# piezo-preamp-tickler_V2-RevX.net
KiCad netlist of a schematic drawn in EAGLE
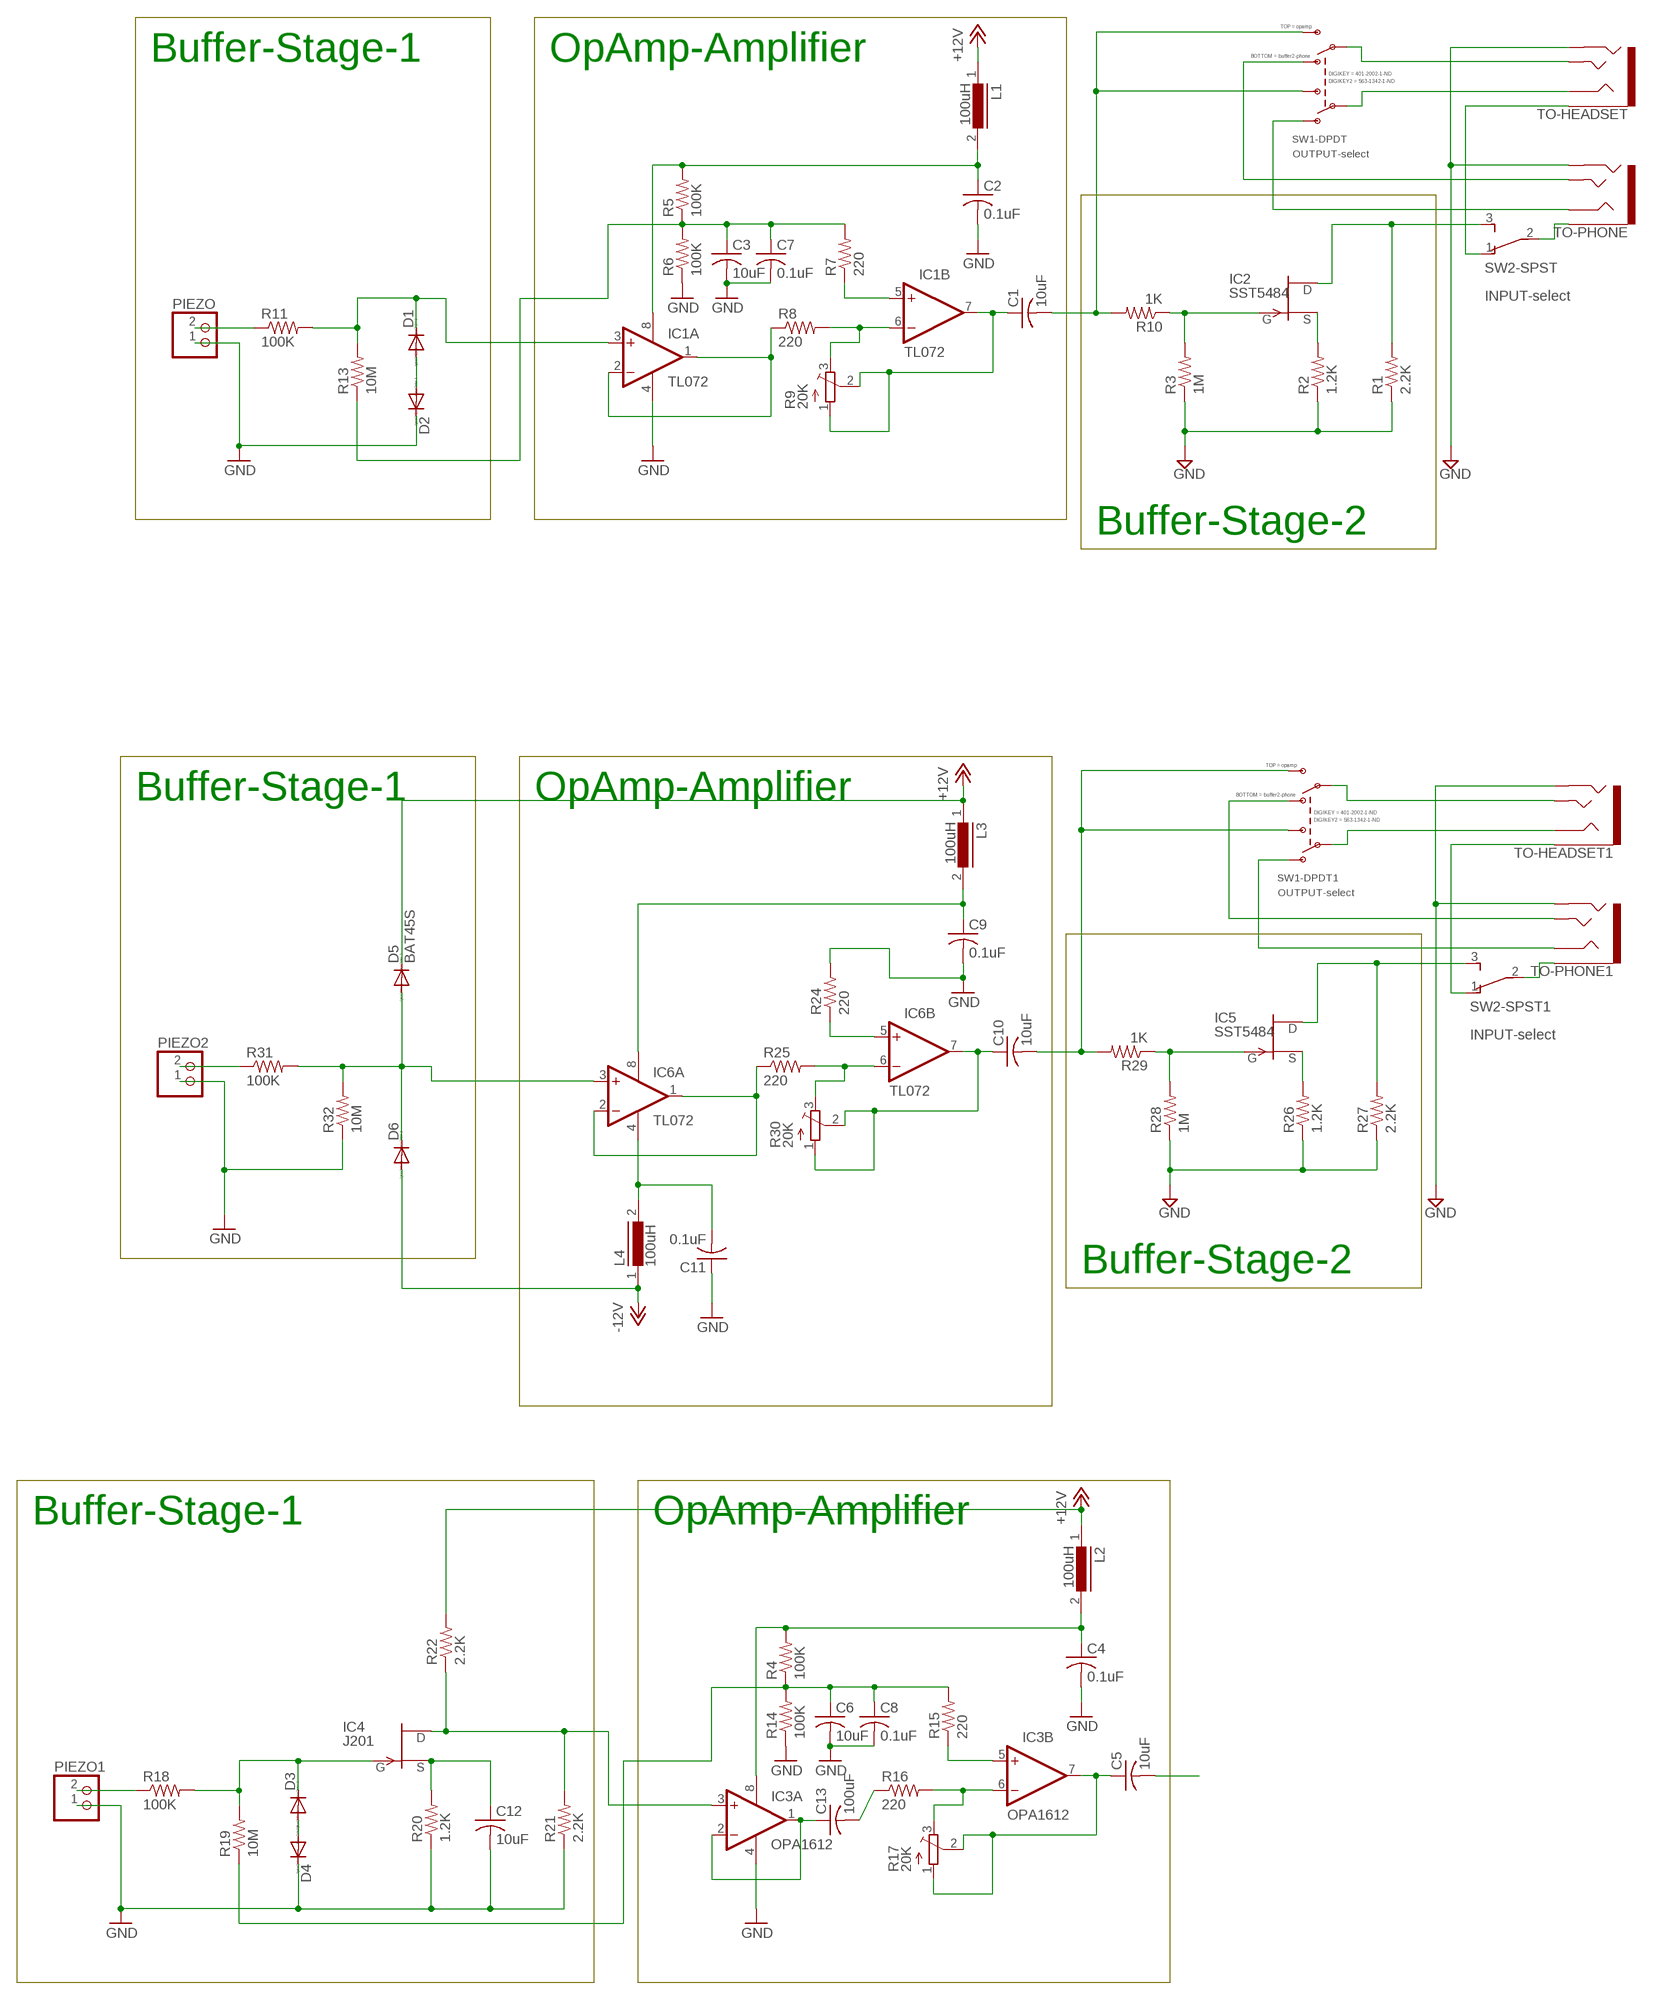
[diagram p0: schematic, sheet 1]
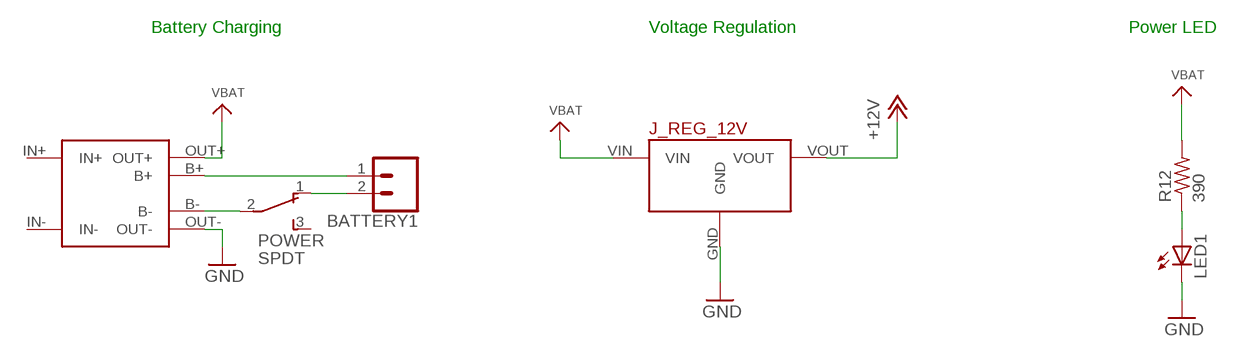
[diagram p1: schematic, sheet 2]

(export (version "E")
  (design (tool "Eeschema 10.0.6"))
  (components
    (comp (ref "C1")
      (value "10uF")
      (footprint "eagle-import:C0805K")
      (libsource (lib "eagle-import") (part "C-USC0805K"))
    )
    (comp (ref "C2")
      (value "0.1uF")
      (footprint "eagle-import:C0805K")
      (libsource (lib "eagle-import") (part "C-USC0805K"))
    )
    (comp (ref "C3")
      (value "10uF")
      (footprint "eagle-import:C0805K")
      (libsource (lib "eagle-import") (part "C-USC0805K"))
    )
    (comp (ref "C4")
      (value "0.1uF")
      (footprint "eagle-import:C0805K")
      (libsource (lib "eagle-import") (part "C-USC0805K"))
    )
    (comp (ref "C5")
      (value "10uF")
      (footprint "eagle-import:C0805K")
      (libsource (lib "eagle-import") (part "C-USC0805K"))
    )
    (comp (ref "C6")
      (value "10uF")
      (footprint "eagle-import:C0805K")
      (libsource (lib "eagle-import") (part "C-USC0805K"))
    )
    (comp (ref "C7")
      (value "0.1uF")
      (footprint "eagle-import:C0805K")
      (libsource (lib "eagle-import") (part "C-USC0805K"))
    )
    (comp (ref "C8")
      (value "0.1uF")
      (footprint "eagle-import:C0805K")
      (libsource (lib "eagle-import") (part "C-USC0805K"))
    )
    (comp (ref "C9")
      (value "0.1uF")
      (footprint "eagle-import:C0805K")
      (libsource (lib "eagle-import") (part "C-USC0805K"))
    )
    (comp (ref "C10")
      (value "10uF")
      (footprint "eagle-import:C0805K")
      (libsource (lib "eagle-import") (part "C-USC0805K"))
    )
    (comp (ref "C11")
      (value "0.1uF")
      (footprint "eagle-import:C0805K")
      (libsource (lib "eagle-import") (part "C-USC0805K"))
    )
    (comp (ref "C12")
      (value "10uF")
      (footprint "eagle-import:C0805K")
      (libsource (lib "eagle-import") (part "C-USC0805K"))
    )
    (comp (ref "C13")
      (value "100uF")
      (footprint "eagle-import:C0805K")
      (libsource (lib "eagle-import") (part "C-USC0805K"))
    )
    (comp (ref "D1")
      (value "DIODE-SOD123")
      (footprint "eagle-import:SOD123")
      (libsource (lib "eagle-import") (part "DIODE-SOD123"))
    )
    (comp (ref "D2")
      (value "DIODE-SOD123")
      (footprint "eagle-import:SOD123")
      (libsource (lib "eagle-import") (part "DIODE-SOD123"))
    )
    (comp (ref "D3")
      (value "DIODE-SOD123")
      (footprint "eagle-import:SOD123")
      (libsource (lib "eagle-import") (part "DIODE-SOD123"))
    )
    (comp (ref "D4")
      (value "DIODE-SOD123")
      (footprint "eagle-import:SOD123")
      (libsource (lib "eagle-import") (part "DIODE-SOD123"))
    )
    (comp (ref "D5")
      (value "BAT45S")
      (footprint "eagle-import:SOD123")
      (libsource (lib "eagle-import") (part "DIODE-SOD123"))
    )
    (comp (ref "D6")
      (value "DIODE-SOD123")
      (footprint "eagle-import:SOD123")
      (libsource (lib "eagle-import") (part "DIODE-SOD123"))
    )
    (comp (ref "IC1")
      (value "TL072")
      (footprint "eagle-import:SO08")
      (libsource (lib "eagle-import") (part "OPA2UA134"))
    )
    (comp (ref "IC2")
      (value "SST5484")
      (footprint "eagle-import:SOT23")
      (libsource (lib "eagle-import") (part "?548SST4"))
    )
    (comp (ref "IC3")
      (value "OPA1612")
      (footprint "eagle-import:SO08")
      (libsource (lib "eagle-import") (part "OPA2UA134"))
    )
    (comp (ref "IC4")
      (value "J201")
      (footprint "eagle-import:SOT23")
      (libsource (lib "eagle-import") (part "?548SST4"))
    )
    (comp (ref "IC5")
      (value "SST5484")
      (footprint "eagle-import:SOT23")
      (libsource (lib "eagle-import") (part "?548SST4"))
    )
    (comp (ref "IC6")
      (value "TL072")
      (footprint "eagle-import:SO08")
      (libsource (lib "eagle-import") (part "OPA2UA134"))
    )
    (comp (ref "L1")
      (value "100uH")
      (footprint "eagle-import:LBC-SE")
      (libsource (lib "eagle-import") (part "LBC-SE"))
    )
    (comp (ref "L2")
      (value "100uH")
      (footprint "eagle-import:LBC-SE")
      (libsource (lib "eagle-import") (part "LBC-SE"))
    )
    (comp (ref "L3")
      (value "100uH")
      (footprint "eagle-import:LBC-SE")
      (libsource (lib "eagle-import") (part "LBC-SE"))
    )
    (comp (ref "L4")
      (value "100uH")
      (footprint "eagle-import:LBC-SE")
      (libsource (lib "eagle-import") (part "LBC-SE"))
    )
    (comp (ref "PIEZO")
      (value "JST_2PIN-THM")
      (footprint "eagle-import:JST-PH-2-THM")
      (libsource (lib "eagle-import") (part "JST_2PIN-THM"))
    )
    (comp (ref "PIEZO1")
      (value "JST_2PIN-THM")
      (footprint "eagle-import:JST-PH-2-THM")
      (libsource (lib "eagle-import") (part "JST_2PIN-THM"))
    )
    (comp (ref "PIEZO2")
      (value "JST_2PIN-THM")
      (footprint "eagle-import:JST-PH-2-THM")
      (libsource (lib "eagle-import") (part "JST_2PIN-THM"))
    )
    (comp (ref "R1")
      (value "2.2K")
      (footprint "eagle-import:R0603")
      (libsource (lib "eagle-import") (part "R-US_R0603"))
    )
    (comp (ref "R2")
      (value "1.2K")
      (footprint "eagle-import:R0603")
      (libsource (lib "eagle-import") (part "R-US_R0603"))
    )
    (comp (ref "R3")
      (value "1M")
      (footprint "eagle-import:R0603")
      (libsource (lib "eagle-import") (part "R-US_R0603"))
    )
    (comp (ref "R4")
      (value "100K")
      (footprint "eagle-import:R0603")
      (libsource (lib "eagle-import") (part "R-US_R0603"))
    )
    (comp (ref "R5")
      (value "100K")
      (footprint "eagle-import:R0603")
      (libsource (lib "eagle-import") (part "R-US_R0603"))
    )
    (comp (ref "R6")
      (value "100K")
      (footprint "eagle-import:R0603")
      (libsource (lib "eagle-import") (part "R-US_R0603"))
    )
    (comp (ref "R7")
      (value "220")
      (footprint "eagle-import:R0603")
      (libsource (lib "eagle-import") (part "R-US_R0603"))
    )
    (comp (ref "R8")
      (value "220")
      (footprint "eagle-import:R0603")
      (libsource (lib "eagle-import") (part "R-US_R0603"))
    )
    (comp (ref "R9")
      (value "20K")
      (footprint "eagle-import:TC33X")
      (libsource (lib "eagle-import") (part "TRIMPOTTC33X"))
    )
    (comp (ref "R10")
      (value "1K")
      (footprint "eagle-import:R0603")
      (libsource (lib "eagle-import") (part "R-US_R0603"))
    )
    (comp (ref "R11")
      (value "100K")
      (footprint "eagle-import:R0603")
      (libsource (lib "eagle-import") (part "R-US_R0603"))
    )
    (comp (ref "R13")
      (value "10M")
      (footprint "eagle-import:R0603")
      (libsource (lib "eagle-import") (part "R-US_R0603"))
    )
    (comp (ref "R14")
      (value "100K")
      (footprint "eagle-import:R0603")
      (libsource (lib "eagle-import") (part "R-US_R0603"))
    )
    (comp (ref "R15")
      (value "220")
      (footprint "eagle-import:R0603")
      (libsource (lib "eagle-import") (part "R-US_R0603"))
    )
    (comp (ref "R16")
      (value "220")
      (footprint "eagle-import:R0603")
      (libsource (lib "eagle-import") (part "R-US_R0603"))
    )
    (comp (ref "R17")
      (value "20K")
      (footprint "eagle-import:TC33X")
      (libsource (lib "eagle-import") (part "TRIMPOTTC33X"))
    )
    (comp (ref "R18")
      (value "100K")
      (footprint "eagle-import:R0603")
      (libsource (lib "eagle-import") (part "R-US_R0603"))
    )
    (comp (ref "R19")
      (value "10M")
      (footprint "eagle-import:R0603")
      (libsource (lib "eagle-import") (part "R-US_R0603"))
    )
    (comp (ref "R20")
      (value "1.2K")
      (footprint "eagle-import:R0603")
      (libsource (lib "eagle-import") (part "R-US_R0603"))
    )
    (comp (ref "R21")
      (value "2.2K")
      (footprint "eagle-import:R0603")
      (libsource (lib "eagle-import") (part "R-US_R0603"))
    )
    (comp (ref "R22")
      (value "2.2K")
      (footprint "eagle-import:R0603")
      (libsource (lib "eagle-import") (part "R-US_R0603"))
    )
    (comp (ref "R24")
      (value "220")
      (footprint "eagle-import:R0603")
      (libsource (lib "eagle-import") (part "R-US_R0603"))
    )
    (comp (ref "R25")
      (value "220")
      (footprint "eagle-import:R0603")
      (libsource (lib "eagle-import") (part "R-US_R0603"))
    )
    (comp (ref "R26")
      (value "1.2K")
      (footprint "eagle-import:R0603")
      (libsource (lib "eagle-import") (part "R-US_R0603"))
    )
    (comp (ref "R27")
      (value "2.2K")
      (footprint "eagle-import:R0603")
      (libsource (lib "eagle-import") (part "R-US_R0603"))
    )
    (comp (ref "R28")
      (value "1M")
      (footprint "eagle-import:R0603")
      (libsource (lib "eagle-import") (part "R-US_R0603"))
    )
    (comp (ref "R29")
      (value "1K")
      (footprint "eagle-import:R0603")
      (libsource (lib "eagle-import") (part "R-US_R0603"))
    )
    (comp (ref "R30")
      (value "20K")
      (footprint "eagle-import:TC33X")
      (libsource (lib "eagle-import") (part "TRIMPOTTC33X"))
    )
    (comp (ref "R31")
      (value "100K")
      (footprint "eagle-import:R0603")
      (libsource (lib "eagle-import") (part "R-US_R0603"))
    )
    (comp (ref "R32")
      (value "10M")
      (footprint "eagle-import:R0603")
      (libsource (lib "eagle-import") (part "R-US_R0603"))
    )
    (comp (ref "SW1-DPDT")
      (value "OUTPUT-select")
      (footprint "eagle-import:DPDT_SMT_JS202011SCQN")
      (fields
        (field (name "BOTTOM") "buffer2-phone")
        (field (name "DIGIKEY") "401-2002-1-ND")
        (field (name "DIGIKEY2") "563-1342-1-ND")
        (field (name "TOP") "opamp")
      )
      (libsource (lib "eagle-import") (part "SWITCH_DPDT"))
    )
    (comp (ref "SW1-DPDT1")
      (value "OUTPUT-select")
      (footprint "eagle-import:DPDT_SMT_JS202011SCQN")
      (fields
        (field (name "BOTTOM") "buffer2-phone")
        (field (name "DIGIKEY") "401-2002-1-ND")
        (field (name "DIGIKEY2") "563-1342-1-ND")
        (field (name "TOP") "opamp")
      )
      (libsource (lib "eagle-import") (part "SWITCH_DPDT"))
    )
    (comp (ref "SW2-SPST")
      (value "INPUT-select")
      (footprint "eagle-import:SWITCH_SPDT-TE-CONNECT")
      (libsource (lib "eagle-import") (part "SWITCH_SPDTTE-CONNECT"))
    )
    (comp (ref "SW2-SPST1")
      (value "INPUT-select")
      (footprint "eagle-import:SWITCH_SPDT-TE-CONNECT")
      (libsource (lib "eagle-import") (part "SWITCH_SPDTTE-CONNECT"))
    )
    (comp (ref "TO-HEADSET")
      (value "AUDIO-JACK3LGPADS")
      (footprint "eagle-import:AUDIO-JACK-TRRS-SMD")
      (libsource (lib "eagle-import") (part "AUDIO-JACK3LGPADS"))
    )
    (comp (ref "TO-HEADSET1")
      (value "AUDIO-JACK3LGPADS")
      (footprint "eagle-import:AUDIO-JACK-TRRS-SMD")
      (libsource (lib "eagle-import") (part "AUDIO-JACK3LGPADS"))
    )
    (comp (ref "TO-PHONE")
      (value "AUDIO-JACK3LGPADS")
      (footprint "eagle-import:AUDIO-JACK-TRRS-SMD")
      (libsource (lib "eagle-import") (part "AUDIO-JACK3LGPADS"))
    )
    (comp (ref "TO-PHONE1")
      (value "AUDIO-JACK3LGPADS")
      (footprint "eagle-import:AUDIO-JACK-TRRS-SMD")
      (libsource (lib "eagle-import") (part "AUDIO-JACK3LGPADS"))
    )
    (comp (ref "BATTERY1")
      (value "CONN_02LOCK")
      (footprint "eagle-import:1X02_LOCK")
      (libsource (lib "eagle-import") (part "CONN_02LOCK"))
    )
    (comp (ref "J_REG_12V")
      (value "POLOLU_VOLTAGE_REGULATORS_3PIN")
      (footprint "eagle-import:POLOLU_5V-12V_STEPUP_U3V12F5-U3V12F12")
      (libsource (lib "eagle-import") (part "POLOLU_VOLTAGE_REGULATORS_3PIN"))
    )
    (comp (ref "LED1")
      (value "LED3MM")
      (footprint "eagle-import:LED3MM")
      (libsource (lib "eagle-import") (part "LED3MM"))
    )
    (comp (ref "POWER")
      (value "SPDT")
      (footprint "eagle-import:SWITCH_SPDT-TE-CONNECT")
      (libsource (lib "eagle-import") (part "SWITCH_SPDTTE-CONNECT"))
    )
    (comp (ref "R12")
      (value "390")
      (footprint "eagle-import:R0805")
      (libsource (lib "eagle-import") (part "R-US_R0805"))
    )
    (comp (ref "USB-LIPO-CHARGER")
      (value "TP4056-MODULE")
      (footprint "eagle-import:TP4056-LITHIUM-PROTECTED-MODULE")
      (libsource (lib "eagle-import") (part "TP4056-MODULE"))
    )
  )
  (nets
    (net (code "1") (name "+12V") (class "Default")
      (node (ref "D5") (pin "C") (pinfunction "C_C") (pintype "passive"))
      (node (ref "J_REG_12V") (pin "VOUT") (pinfunction "VOUT_VOUT") (pintype "bidirectional"))
      (node (ref "L1") (pin "1") (pinfunction "1_1") (pintype "passive"))
      (node (ref "L2") (pin "1") (pinfunction "1_1") (pintype "passive"))
      (node (ref "L3") (pin "1") (pinfunction "1_1") (pintype "passive"))
      (node (ref "R22") (pin "2") (pinfunction "2_2") (pintype "passive"))
    )
    (net (code "2") (name "-12V") (class "Default")
      (node (ref "D6") (pin "A") (pinfunction "A_A") (pintype "passive"))
      (node (ref "L4") (pin "1") (pinfunction "1_1") (pintype "passive"))
    )
    (net (code "3") (name "GND") (class "Default")
      (node (ref "C11") (pin "1") (pinfunction "1_1") (pintype "passive"))
      (node (ref "C12") (pin "2") (pinfunction "2_2") (pintype "passive"))
      (node (ref "C2") (pin "2") (pinfunction "2_2") (pintype "passive"))
      (node (ref "C3") (pin "2") (pinfunction "2_2") (pintype "passive"))
      (node (ref "C4") (pin "2") (pinfunction "2_2") (pintype "passive"))
      (node (ref "C6") (pin "2") (pinfunction "2_2") (pintype "passive"))
      (node (ref "C7") (pin "2") (pinfunction "2_2") (pintype "passive"))
      (node (ref "C8") (pin "2") (pinfunction "2_2") (pintype "passive"))
      (node (ref "C9") (pin "2") (pinfunction "2_2") (pintype "passive"))
      (node (ref "D2") (pin "C") (pinfunction "C_C") (pintype "passive"))
      (node (ref "D4") (pin "C") (pinfunction "C_C") (pintype "passive"))
      (node (ref "IC1") (pin "4") (pinfunction "V-_4") (pintype "power_in"))
      (node (ref "IC3") (pin "4") (pinfunction "V-_4") (pintype "power_in"))
      (node (ref "J_REG_12V") (pin "GND") (pinfunction "GND_GND") (pintype "bidirectional"))
      (node (ref "LED1") (pin "K") (pinfunction "C_K") (pintype "passive"))
      (node (ref "PIEZO") (pin "1") (pinfunction "2_1") (pintype "passive"))
      (node (ref "PIEZO1") (pin "1") (pinfunction "2_1") (pintype "passive"))
      (node (ref "PIEZO2") (pin "1") (pinfunction "2_1") (pintype "passive"))
      (node (ref "R1") (pin "1") (pinfunction "1_1") (pintype "passive"))
      (node (ref "R14") (pin "1") (pinfunction "1_1") (pintype "passive"))
      (node (ref "R2") (pin "1") (pinfunction "1_1") (pintype "passive"))
      (node (ref "R20") (pin "1") (pinfunction "1_1") (pintype "passive"))
      (node (ref "R21") (pin "1") (pinfunction "1_1") (pintype "passive"))
      (node (ref "R24") (pin "2") (pinfunction "2_2") (pintype "passive"))
      (node (ref "R26") (pin "1") (pinfunction "1_1") (pintype "passive"))
      (node (ref "R27") (pin "1") (pinfunction "1_1") (pintype "passive"))
      (node (ref "R28") (pin "1") (pinfunction "1_1") (pintype "passive"))
      (node (ref "R3") (pin "1") (pinfunction "1_1") (pintype "passive"))
      (node (ref "R32") (pin "1") (pinfunction "1_1") (pintype "passive"))
      (node (ref "R6") (pin "1") (pinfunction "1_1") (pintype "passive"))
      (node (ref "TO-HEADSET") (pin "RING2") (pinfunction "RING2_RING2") (pintype "bidirectional"))
      (node (ref "TO-HEADSET1") (pin "RING2") (pinfunction "RING2_RING2") (pintype "bidirectional"))
      (node (ref "TO-PHONE") (pin "RING2") (pinfunction "RING2_RING2") (pintype "bidirectional"))
      (node (ref "TO-PHONE1") (pin "RING2") (pinfunction "RING2_RING2") (pintype "bidirectional"))
      (node (ref "USB-LIPO-CHARGER") (pin "OUT-") (pinfunction "OUT-_OUT-") (pintype "power_in"))
    )
    (net (code "4") (name "IN+") (class "Default")
      (node (ref "USB-LIPO-CHARGER") (pin "IN+") (pinfunction "IN+_IN+") (pintype "power_in"))
    )
    (net (code "5") (name "IN-") (class "Default")
      (node (ref "USB-LIPO-CHARGER") (pin "IN-") (pinfunction "IN-_IN-") (pintype "power_in"))
    )
    (net (code "6") (name "Net-(BATTERY1-Pad1)") (class "Default")
      (node (ref "BATTERY1") (pin "1") (pinfunction "1_1") (pintype "passive"))
      (node (ref "USB-LIPO-CHARGER") (pin "B+") (pinfunction "B+_B+") (pintype "power_in"))
    )
    (net (code "7") (name "Net-(BATTERY1-Pad2)") (class "Default")
      (node (ref "BATTERY1") (pin "2") (pinfunction "2_2") (pintype "passive"))
      (node (ref "POWER") (pin "1") (pinfunction "1_1") (pintype "passive"))
    )
    (net (code "8") (name "Net-(C3-Pad1)") (class "Default")
      (node (ref "C3") (pin "1") (pinfunction "1_1") (pintype "passive"))
      (node (ref "C7") (pin "1") (pinfunction "1_1") (pintype "passive"))
      (node (ref "R13") (pin "1") (pinfunction "1_1") (pintype "passive"))
      (node (ref "R5") (pin "1") (pinfunction "1_1") (pintype "passive"))
      (node (ref "R6") (pin "2") (pinfunction "2_2") (pintype "passive"))
      (node (ref "R7") (pin "2") (pinfunction "2_2") (pintype "passive"))
    )
    (net (code "9") (name "Net-(C6-Pad1)") (class "Default")
      (node (ref "C6") (pin "1") (pinfunction "1_1") (pintype "passive"))
      (node (ref "C8") (pin "1") (pinfunction "1_1") (pintype "passive"))
      (node (ref "R14") (pin "2") (pinfunction "2_2") (pintype "passive"))
      (node (ref "R15") (pin "2") (pinfunction "2_2") (pintype "passive"))
      (node (ref "R19") (pin "1") (pinfunction "1_1") (pintype "passive"))
      (node (ref "R4") (pin "1") (pinfunction "1_1") (pintype "passive"))
    )
    (net (code "10") (name "Net-(C13-Pad2)") (class "Default")
      (node (ref "C13") (pin "2") (pinfunction "2_2") (pintype "passive"))
      (node (ref "R16") (pin "1") (pinfunction "1_1") (pintype "passive"))
    )
    (net (code "11") (name "Net-(D1-PadA)") (class "Default")
      (node (ref "D1") (pin "A") (pinfunction "A_A") (pintype "passive"))
      (node (ref "D2") (pin "A") (pinfunction "A_A") (pintype "passive"))
    )
    (net (code "12") (name "Net-(D3-PadA)") (class "Default")
      (node (ref "D3") (pin "A") (pinfunction "A_A") (pintype "passive"))
      (node (ref "D4") (pin "A") (pinfunction "A_A") (pintype "passive"))
    )
    (net (code "13") (name "Net-(IC1A-+IN)") (class "Default")
      (node (ref "D1") (pin "C") (pinfunction "C_C") (pintype "passive"))
      (node (ref "IC1") (pin "3") (pinfunction "+IN_3") (pintype "input"))
      (node (ref "R11") (pin "2") (pinfunction "2_2") (pintype "passive"))
      (node (ref "R13") (pin "2") (pinfunction "2_2") (pintype "passive"))
    )
    (net (code "14") (name "Net-(IC1A--IN)") (class "Default")
      (node (ref "IC1") (pin "1") (pinfunction "OUT_1") (pintype "output"))
      (node (ref "IC1") (pin "2") (pinfunction "-IN_2") (pintype "input"))
      (node (ref "R8") (pin "1") (pinfunction "1_1") (pintype "passive"))
    )
    (net (code "15") (name "Net-(IC1A-V+)") (class "Default")
      (node (ref "C2") (pin "1") (pinfunction "1_1") (pintype "passive"))
      (node (ref "IC1") (pin "8") (pinfunction "V+_8") (pintype "power_in"))
      (node (ref "L1") (pin "2") (pinfunction "2_2") (pintype "passive"))
      (node (ref "R5") (pin "2") (pinfunction "2_2") (pintype "passive"))
    )
    (net (code "16") (name "Net-(IC1B-+IN)") (class "Default")
      (node (ref "IC1") (pin "5") (pinfunction "+IN_5") (pintype "input"))
      (node (ref "R7") (pin "1") (pinfunction "1_1") (pintype "passive"))
    )
    (net (code "17") (name "Net-(IC1B--IN)") (class "Default")
      (node (ref "IC1") (pin "6") (pinfunction "-IN_6") (pintype "input"))
      (node (ref "R8") (pin "2") (pinfunction "2_2") (pintype "passive"))
      (node (ref "R9") (pin "3") (pinfunction "E_3") (pintype "passive"))
    )
    (net (code "18") (name "Net-(IC1B-OUT)") (class "Default")
      (node (ref "C1") (pin "1") (pinfunction "1_1") (pintype "passive"))
      (node (ref "IC1") (pin "7") (pinfunction "OUT_7") (pintype "output"))
      (node (ref "R9") (pin "1") (pinfunction "A_1") (pintype "passive"))
      (node (ref "R9") (pin "2") (pinfunction "S_2") (pintype "passive"))
    )
    (net (code "19") (name "Net-(IC2-D)") (class "Default")
      (node (ref "IC2") (pin "1") (pinfunction "D_1") (pintype "passive"))
      (node (ref "R1") (pin "2") (pinfunction "2_2") (pintype "passive"))
      (node (ref "SW2-SPST") (pin "3") (pinfunction "3_3") (pintype "passive"))
    )
    (net (code "20") (name "Net-(IC2-G)") (class "Default")
      (node (ref "IC2") (pin "3") (pinfunction "G_3") (pintype "passive"))
      (node (ref "R10") (pin "1") (pinfunction "1_1") (pintype "passive"))
      (node (ref "R3") (pin "2") (pinfunction "2_2") (pintype "passive"))
    )
    (net (code "21") (name "Net-(IC2-S)") (class "Default")
      (node (ref "IC2") (pin "2") (pinfunction "S_2") (pintype "passive"))
      (node (ref "R2") (pin "2") (pinfunction "2_2") (pintype "passive"))
    )
    (net (code "22") (name "Net-(IC3A-+IN)") (class "Default")
      (node (ref "IC3") (pin "3") (pinfunction "+IN_3") (pintype "input"))
      (node (ref "IC4") (pin "1") (pinfunction "D_1") (pintype "passive"))
      (node (ref "R21") (pin "2") (pinfunction "2_2") (pintype "passive"))
      (node (ref "R22") (pin "1") (pinfunction "1_1") (pintype "passive"))
    )
    (net (code "23") (name "Net-(IC3A--IN)") (class "Default")
      (node (ref "C13") (pin "1") (pinfunction "1_1") (pintype "passive"))
      (node (ref "IC3") (pin "1") (pinfunction "OUT_1") (pintype "output"))
      (node (ref "IC3") (pin "2") (pinfunction "-IN_2") (pintype "input"))
    )
    (net (code "24") (name "Net-(IC3A-V+)") (class "Default")
      (node (ref "C4") (pin "1") (pinfunction "1_1") (pintype "passive"))
      (node (ref "IC3") (pin "8") (pinfunction "V+_8") (pintype "power_in"))
      (node (ref "L2") (pin "2") (pinfunction "2_2") (pintype "passive"))
      (node (ref "R4") (pin "2") (pinfunction "2_2") (pintype "passive"))
    )
    (net (code "25") (name "Net-(IC3B-+IN)") (class "Default")
      (node (ref "IC3") (pin "5") (pinfunction "+IN_5") (pintype "input"))
      (node (ref "R15") (pin "1") (pinfunction "1_1") (pintype "passive"))
    )
    (net (code "26") (name "Net-(IC3B--IN)") (class "Default")
      (node (ref "IC3") (pin "6") (pinfunction "-IN_6") (pintype "input"))
      (node (ref "R16") (pin "2") (pinfunction "2_2") (pintype "passive"))
      (node (ref "R17") (pin "3") (pinfunction "E_3") (pintype "passive"))
    )
    (net (code "27") (name "Net-(IC3B-OUT)") (class "Default")
      (node (ref "C5") (pin "1") (pinfunction "1_1") (pintype "passive"))
      (node (ref "IC3") (pin "7") (pinfunction "OUT_7") (pintype "output"))
      (node (ref "R17") (pin "1") (pinfunction "A_1") (pintype "passive"))
      (node (ref "R17") (pin "2") (pinfunction "S_2") (pintype "passive"))
    )
    (net (code "28") (name "Net-(IC4-G)") (class "Default")
      (node (ref "D3") (pin "C") (pinfunction "C_C") (pintype "passive"))
      (node (ref "IC4") (pin "3") (pinfunction "G_3") (pintype "passive"))
      (node (ref "R18") (pin "2") (pinfunction "2_2") (pintype "passive"))
      (node (ref "R19") (pin "2") (pinfunction "2_2") (pintype "passive"))
    )
    (net (code "29") (name "Net-(IC4-S)") (class "Default")
      (node (ref "C12") (pin "1") (pinfunction "1_1") (pintype "passive"))
      (node (ref "IC4") (pin "2") (pinfunction "S_2") (pintype "passive"))
      (node (ref "R20") (pin "2") (pinfunction "2_2") (pintype "passive"))
    )
    (net (code "30") (name "Net-(IC5-D)") (class "Default")
      (node (ref "IC5") (pin "1") (pinfunction "D_1") (pintype "passive"))
      (node (ref "R27") (pin "2") (pinfunction "2_2") (pintype "passive"))
      (node (ref "SW2-SPST1") (pin "3") (pinfunction "3_3") (pintype "passive"))
    )
    (net (code "31") (name "Net-(IC5-G)") (class "Default")
      (node (ref "IC5") (pin "3") (pinfunction "G_3") (pintype "passive"))
      (node (ref "R28") (pin "2") (pinfunction "2_2") (pintype "passive"))
      (node (ref "R29") (pin "1") (pinfunction "1_1") (pintype "passive"))
    )
    (net (code "32") (name "Net-(IC5-S)") (class "Default")
      (node (ref "IC5") (pin "2") (pinfunction "S_2") (pintype "passive"))
      (node (ref "R26") (pin "2") (pinfunction "2_2") (pintype "passive"))
    )
    (net (code "33") (name "Net-(IC6A-+IN)") (class "Default")
      (node (ref "D5") (pin "A") (pinfunction "A_A") (pintype "passive"))
      (node (ref "D6") (pin "C") (pinfunction "C_C") (pintype "passive"))
      (node (ref "IC6") (pin "3") (pinfunction "+IN_3") (pintype "input"))
      (node (ref "R31") (pin "2") (pinfunction "2_2") (pintype "passive"))
      (node (ref "R32") (pin "2") (pinfunction "2_2") (pintype "passive"))
    )
    (net (code "34") (name "Net-(IC6A--IN)") (class "Default")
      (node (ref "IC6") (pin "1") (pinfunction "OUT_1") (pintype "output"))
      (node (ref "IC6") (pin "2") (pinfunction "-IN_2") (pintype "input"))
      (node (ref "R25") (pin "1") (pinfunction "1_1") (pintype "passive"))
    )
    (net (code "35") (name "Net-(IC6A-V+)") (class "Default")
      (node (ref "C9") (pin "1") (pinfunction "1_1") (pintype "passive"))
      (node (ref "IC6") (pin "8") (pinfunction "V+_8") (pintype "power_in"))
      (node (ref "L3") (pin "2") (pinfunction "2_2") (pintype "passive"))
    )
    (net (code "36") (name "Net-(IC6A-V-)") (class "Default")
      (node (ref "C11") (pin "2") (pinfunction "2_2") (pintype "passive"))
      (node (ref "IC6") (pin "4") (pinfunction "V-_4") (pintype "power_in"))
      (node (ref "L4") (pin "2") (pinfunction "2_2") (pintype "passive"))
    )
    (net (code "37") (name "Net-(IC6B-+IN)") (class "Default")
      (node (ref "IC6") (pin "5") (pinfunction "+IN_5") (pintype "input"))
      (node (ref "R24") (pin "1") (pinfunction "1_1") (pintype "passive"))
    )
    (net (code "38") (name "Net-(IC6B--IN)") (class "Default")
      (node (ref "IC6") (pin "6") (pinfunction "-IN_6") (pintype "input"))
      (node (ref "R25") (pin "2") (pinfunction "2_2") (pintype "passive"))
      (node (ref "R30") (pin "3") (pinfunction "E_3") (pintype "passive"))
    )
    (net (code "39") (name "Net-(IC6B-OUT)") (class "Default")
      (node (ref "C10") (pin "1") (pinfunction "1_1") (pintype "passive"))
      (node (ref "IC6") (pin "7") (pinfunction "OUT_7") (pintype "output"))
      (node (ref "R30") (pin "1") (pinfunction "A_1") (pintype "passive"))
      (node (ref "R30") (pin "2") (pinfunction "S_2") (pintype "passive"))
    )
    (net (code "40") (name "Net-(LED1-PadA)") (class "Default")
      (node (ref "LED1") (pin "A") (pinfunction "A_A") (pintype "passive"))
      (node (ref "R12") (pin "1") (pinfunction "1_1") (pintype "passive"))
    )
    (net (code "41") (name "Net-(PIEZO-1)") (class "Default")
      (node (ref "PIEZO") (pin "2") (pinfunction "1_2") (pintype "passive"))
      (node (ref "R11") (pin "1") (pinfunction "1_1") (pintype "passive"))
    )
    (net (code "42") (name "Net-(PIEZO1-1)") (class "Default")
      (node (ref "PIEZO1") (pin "2") (pinfunction "1_2") (pintype "passive"))
      (node (ref "R18") (pin "1") (pinfunction "1_1") (pintype "passive"))
    )
    (net (code "43") (name "Net-(PIEZO2-1)") (class "Default")
      (node (ref "PIEZO2") (pin "2") (pinfunction "1_2") (pintype "passive"))
      (node (ref "R31") (pin "1") (pinfunction "1_1") (pintype "passive"))
    )
    (net (code "44") (name "Net-(POWER-Pad2)") (class "Default")
      (node (ref "POWER") (pin "2") (pinfunction "2_2") (pintype "passive"))
      (node (ref "USB-LIPO-CHARGER") (pin "B-") (pinfunction "B-_B-") (pintype "power_in"))
    )
    (net (code "45") (name "Net-(SW1-DPDT-O1)") (class "Default")
      (node (ref "SW1-DPDT") (pin "P$1") (pinfunction "O1_P$1") (pintype "passive"))
      (node (ref "TO-PHONE") (pin "RING1") (pinfunction "RING1_RING1") (pintype "bidirectional"))
    )
    (net (code "46") (name "Net-(SW1-DPDT-O2)") (class "Default")
      (node (ref "SW1-DPDT") (pin "P$6") (pinfunction "O2_P$6") (pintype "passive"))
      (node (ref "TO-PHONE") (pin "TIP") (pinfunction "TIP_TIP") (pintype "bidirectional"))
    )
    (net (code "47") (name "Net-(SW1-DPDT-P1)") (class "Default")
      (node (ref "SW1-DPDT") (pin "P$2") (pinfunction "P1_P$2") (pintype "passive"))
      (node (ref "TO-HEADSET") (pin "RING1") (pinfunction "RING1_RING1") (pintype "bidirectional"))
    )
    (net (code "48") (name "Net-(SW1-DPDT-P2)") (class "Default")
      (node (ref "SW1-DPDT") (pin "P$5") (pinfunction "P2_P$5") (pintype "passive"))
      (node (ref "TO-HEADSET") (pin "TIP") (pinfunction "TIP_TIP") (pintype "bidirectional"))
    )
    (net (code "49") (name "Net-(SW1-DPDT-S1)") (class "Default")
      (node (ref "C1") (pin "2") (pinfunction "2_2") (pintype "passive"))
      (node (ref "R10") (pin "2") (pinfunction "2_2") (pintype "passive"))
      (node (ref "SW1-DPDT") (pin "P$3") (pinfunction "S1_P$3") (pintype "passive"))
      (node (ref "SW1-DPDT") (pin "P$4") (pinfunction "S2_P$4") (pintype "passive"))
    )
    (net (code "50") (name "Net-(SW1-DPDT1-O1)") (class "Default")
      (node (ref "SW1-DPDT1") (pin "P$1") (pinfunction "O1_P$1") (pintype "passive"))
      (node (ref "TO-PHONE1") (pin "RING1") (pinfunction "RING1_RING1") (pintype "bidirectional"))
    )
    (net (code "51") (name "Net-(SW1-DPDT1-O2)") (class "Default")
      (node (ref "SW1-DPDT1") (pin "P$6") (pinfunction "O2_P$6") (pintype "passive"))
      (node (ref "TO-PHONE1") (pin "TIP") (pinfunction "TIP_TIP") (pintype "bidirectional"))
    )
    (net (code "52") (name "Net-(SW1-DPDT1-P1)") (class "Default")
      (node (ref "SW1-DPDT1") (pin "P$2") (pinfunction "P1_P$2") (pintype "passive"))
      (node (ref "TO-HEADSET1") (pin "RING1") (pinfunction "RING1_RING1") (pintype "bidirectional"))
    )
    (net (code "53") (name "Net-(SW1-DPDT1-P2)") (class "Default")
      (node (ref "SW1-DPDT1") (pin "P$5") (pinfunction "P2_P$5") (pintype "passive"))
      (node (ref "TO-HEADSET1") (pin "TIP") (pinfunction "TIP_TIP") (pintype "bidirectional"))
    )
    (net (code "54") (name "Net-(SW1-DPDT1-S1)") (class "Default")
      (node (ref "C10") (pin "2") (pinfunction "2_2") (pintype "passive"))
      (node (ref "R29") (pin "2") (pinfunction "2_2") (pintype "passive"))
      (node (ref "SW1-DPDT1") (pin "P$3") (pinfunction "S1_P$3") (pintype "passive"))
      (node (ref "SW1-DPDT1") (pin "P$4") (pinfunction "S2_P$4") (pintype "passive"))
    )
    (net (code "55") (name "Net-(SW2-SPST-Pad1)") (class "Default")
      (node (ref "SW2-SPST") (pin "1") (pinfunction "1_1") (pintype "passive"))
      (node (ref "TO-HEADSET") (pin "EARTH") (pinfunction "EARTH_EARTH") (pintype "bidirectional"))
    )
    (net (code "56") (name "Net-(SW2-SPST-Pad2)") (class "Default")
      (node (ref "SW2-SPST") (pin "2") (pinfunction "2_2") (pintype "passive"))
      (node (ref "TO-PHONE") (pin "EARTH") (pinfunction "EARTH_EARTH") (pintype "bidirectional"))
    )
    (net (code "57") (name "Net-(SW2-SPST1-Pad1)") (class "Default")
      (node (ref "SW2-SPST1") (pin "1") (pinfunction "1_1") (pintype "passive"))
      (node (ref "TO-HEADSET1") (pin "EARTH") (pinfunction "EARTH_EARTH") (pintype "bidirectional"))
    )
    (net (code "58") (name "Net-(SW2-SPST1-Pad2)") (class "Default")
      (node (ref "SW2-SPST1") (pin "2") (pinfunction "2_2") (pintype "passive"))
      (node (ref "TO-PHONE1") (pin "EARTH") (pinfunction "EARTH_EARTH") (pintype "bidirectional"))
    )
    (net (code "59") (name "VBAT") (class "Default")
      (node (ref "J_REG_12V") (pin "VIN") (pinfunction "VIN_VIN") (pintype "bidirectional"))
      (node (ref "R12") (pin "2") (pinfunction "2_2") (pintype "passive"))
      (node (ref "USB-LIPO-CHARGER") (pin "OUT+") (pinfunction "OUT+_OUT+") (pintype "power_in"))
    )
    (net (code "60") (name "unconnected-(C5-Pad2)") (class "Default")
      (node (ref "C5") (pin "2") (pinfunction "2_2") (pintype "passive"))
    )
    (net (code "61") (name "unconnected-(POWER-Pad3)") (class "Default")
      (node (ref "POWER") (pin "3") (pinfunction "3_3") (pintype "passive"))
    )
  )
)
